# CP2200.net
KiCad netlist of a schematic drawn in Altium Designer
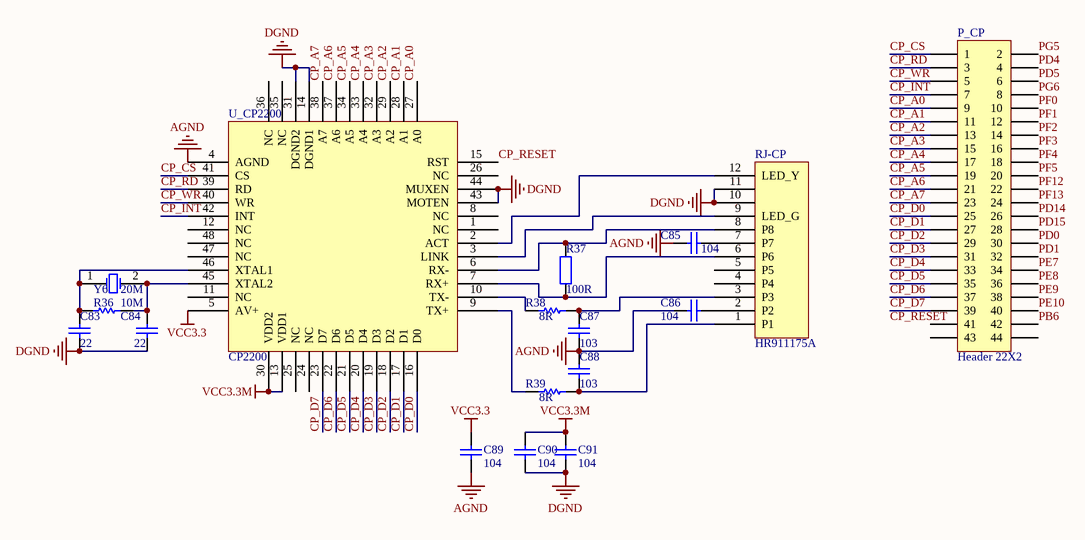
[diagram p0: CP2200.SchDoc]

(export (version "E")
  (design (tool "Eeschema 10.0.6"))
  (components
    (comp (ref "C83")
      (value "22")
      (footprint "SMT-0603")
      (description "Capacitor")
      (fields (field (name "Comment") "Cap") (field (name "PUBLISHER") "Altium Limited"))
      (libsource (lib "Miscellaneous Devices") (part "Cap"))
    )
    (comp (ref "C84")
      (value "22")
      (footprint "SMT-0603")
      (description "Capacitor")
      (fields (field (name "Comment") "Cap") (field (name "PUBLISHER") "Altium Limited"))
      (libsource (lib "Miscellaneous Devices") (part "Cap"))
    )
    (comp (ref "C85")
      (value "104")
      (footprint "SMT-0603")
      (description "Capacitor")
      (fields (field (name "Comment") "Cap") (field (name "PUBLISHER") "Altium Limited"))
      (libsource (lib "Miscellaneous Devices") (part "Cap"))
    )
    (comp (ref "C86")
      (value "104")
      (footprint "SMT-0603")
      (description "Capacitor")
      (fields (field (name "Comment") "Cap") (field (name "PUBLISHER") "Altium Limited"))
      (libsource (lib "Miscellaneous Devices") (part "Cap"))
    )
    (comp (ref "C87")
      (value "103")
      (footprint "SMT-0603")
      (description "Capacitor")
      (fields (field (name "Comment") "Cap") (field (name "PUBLISHER") "Altium Limited"))
      (libsource (lib "Miscellaneous Devices") (part "Cap"))
    )
    (comp (ref "C88")
      (value "103")
      (footprint "SMT-0603")
      (description "Capacitor")
      (fields (field (name "Comment") "Cap") (field (name "PUBLISHER") "Altium Limited"))
      (libsource (lib "Miscellaneous Devices") (part "Cap"))
    )
    (comp (ref "C89")
      (value "104")
      (footprint "SMT-0603")
      (description "Capacitor")
      (fields (field (name "Comment") "Cap") (field (name "PUBLISHER") "Altium Limited"))
      (libsource (lib "Miscellaneous Devices") (part "Cap"))
    )
    (comp (ref "C90")
      (value "104")
      (footprint "SMT-0603")
      (description "Capacitor")
      (fields (field (name "Comment") "Cap") (field (name "PUBLISHER") "Altium Limited"))
      (libsource (lib "Miscellaneous Devices") (part "Cap"))
    )
    (comp (ref "C91")
      (value "104")
      (footprint "SMT-0603")
      (description "Capacitor")
      (fields (field (name "Comment") "Cap") (field (name "PUBLISHER") "Altium Limited"))
      (libsource (lib "Miscellaneous Devices") (part "Cap"))
    )
    (comp (ref "P_CP")
      (value "Header 22X2")
      (footprint "HDR2X22")
      (description "Header, 22-Pin, Dual row")
      (fields (field (name "PUBLISHER") "Altium Limited"))
      (libsource (lib "Miscellaneous Connectors") (part "Header 22X2"))
    )
    (comp (ref "R36")
      (value "10M")
      (footprint "SMT-0603")
      (description "Resistor")
      (fields (field (name "Comment") "Res1") (field (name "PUBLISHER") "Altium Limited"))
      (libsource (lib "Miscellaneous Devices") (part "Res1"))
    )
    (comp (ref "R37")
      (value "100R")
      (footprint "SMT-0603")
      (description "Resistor")
      (fields (field (name "Comment") "Res2") (field (name "PUBLISHER") "Altium Limited"))
      (libsource (lib "Miscellaneous Devices") (part "Res2"))
    )
    (comp (ref "R38")
      (value "8R")
      (footprint "SMT-0603")
      (description "Resistor")
      (fields (field (name "Comment") "Res1") (field (name "PUBLISHER") "Altium Limited"))
      (libsource (lib "Miscellaneous Devices") (part "Res1"))
    )
    (comp (ref "R39")
      (value "8R")
      (footprint "SMT-0603")
      (description "Resistor")
      (fields (field (name "Comment") "Res1") (field (name "PUBLISHER") "Altium Limited"))
      (libsource (lib "Miscellaneous Devices") (part "Res1"))
    )
    (comp (ref "RJ-CP")
      (value "HR911175A")
      (footprint "RJ45-LED")
      (libsource (lib "STM_ALL") (part "RJ-45 HR911175A"))
    )
    (comp (ref "U_CP2200") (value "CP2200") (footprint "LQFP48L") (libsource (lib "STM_ALL") (part "CP2200")))
    (comp (ref "Y6")
      (value "20M")
      (footprint "D-CRYSTAL_UPRIGHT")
      (description "Crystal Oscillator")
      (fields (field (name "PUBLISHER") "Altium Limited"))
      (libsource (lib "Miscellaneous Devices") (part "XTAL"))
    )
  )
  (nets
    (net (code "1") (name "/CP_A0") (class "Default")
      (node (ref "P_CP") (pin "9") (pinfunction "9_9") (pintype "passive"))
      (node (ref "U_CP2200") (pin "27") (pinfunction "A0_27") (pintype "passive"))
    )
    (net (code "2") (name "/CP_A1") (class "Default")
      (node (ref "P_CP") (pin "11") (pinfunction "11_11") (pintype "passive"))
      (node (ref "U_CP2200") (pin "28") (pinfunction "A1_28") (pintype "passive"))
    )
    (net (code "3") (name "/CP_A2") (class "Default")
      (node (ref "P_CP") (pin "13") (pinfunction "13_13") (pintype "passive"))
      (node (ref "U_CP2200") (pin "29") (pinfunction "A2_29") (pintype "passive"))
    )
    (net (code "4") (name "/CP_A3") (class "Default")
      (node (ref "P_CP") (pin "15") (pinfunction "15_15") (pintype "passive"))
      (node (ref "U_CP2200") (pin "32") (pinfunction "A3_32") (pintype "passive"))
    )
    (net (code "5") (name "/CP_A4") (class "Default")
      (node (ref "P_CP") (pin "17") (pinfunction "17_17") (pintype "passive"))
      (node (ref "U_CP2200") (pin "33") (pinfunction "A4_33") (pintype "passive"))
    )
    (net (code "6") (name "/CP_A5") (class "Default")
      (node (ref "P_CP") (pin "19") (pinfunction "19_19") (pintype "passive"))
      (node (ref "U_CP2200") (pin "34") (pinfunction "A5_34") (pintype "passive"))
    )
    (net (code "7") (name "/CP_A6") (class "Default")
      (node (ref "P_CP") (pin "21") (pinfunction "21_21") (pintype "passive"))
      (node (ref "U_CP2200") (pin "37") (pinfunction "A6_37") (pintype "passive"))
    )
    (net (code "8") (name "/CP_A7") (class "Default")
      (node (ref "P_CP") (pin "23") (pinfunction "23_23") (pintype "passive"))
      (node (ref "U_CP2200") (pin "38") (pinfunction "A7_38") (pintype "passive"))
    )
    (net (code "9") (name "/CP_CS") (class "Default")
      (node (ref "P_CP") (pin "1") (pinfunction "1_1") (pintype "passive"))
      (node (ref "U_CP2200") (pin "41") (pinfunction "CS_41") (pintype "passive"))
    )
    (net (code "10") (name "/CP_D0") (class "Default")
      (node (ref "P_CP") (pin "25") (pinfunction "25_25") (pintype "passive"))
      (node (ref "U_CP2200") (pin "16") (pinfunction "D0_16") (pintype "passive"))
    )
    (net (code "11") (name "/CP_D1") (class "Default")
      (node (ref "P_CP") (pin "27") (pinfunction "27_27") (pintype "passive"))
      (node (ref "U_CP2200") (pin "17") (pinfunction "D1_17") (pintype "passive"))
    )
    (net (code "12") (name "/CP_D2") (class "Default")
      (node (ref "P_CP") (pin "29") (pinfunction "29_29") (pintype "passive"))
      (node (ref "U_CP2200") (pin "18") (pinfunction "D2_18") (pintype "passive"))
    )
    (net (code "13") (name "/CP_D3") (class "Default")
      (node (ref "P_CP") (pin "31") (pinfunction "31_31") (pintype "passive"))
      (node (ref "U_CP2200") (pin "19") (pinfunction "D3_19") (pintype "passive"))
    )
    (net (code "14") (name "/CP_D4") (class "Default")
      (node (ref "P_CP") (pin "33") (pinfunction "33_33") (pintype "passive"))
      (node (ref "U_CP2200") (pin "20") (pinfunction "D4_20") (pintype "passive"))
    )
    (net (code "15") (name "/CP_D5") (class "Default")
      (node (ref "P_CP") (pin "35") (pinfunction "35_35") (pintype "passive"))
      (node (ref "U_CP2200") (pin "21") (pinfunction "D5_21") (pintype "passive"))
    )
    (net (code "16") (name "/CP_D6") (class "Default")
      (node (ref "P_CP") (pin "37") (pinfunction "37_37") (pintype "passive"))
      (node (ref "U_CP2200") (pin "22") (pinfunction "D6_22") (pintype "passive"))
    )
    (net (code "17") (name "/CP_D7") (class "Default")
      (node (ref "P_CP") (pin "39") (pinfunction "39_39") (pintype "passive"))
      (node (ref "U_CP2200") (pin "23") (pinfunction "D7_23") (pintype "passive"))
    )
    (net (code "18") (name "/CP_INT") (class "Default")
      (node (ref "P_CP") (pin "7") (pinfunction "7_7") (pintype "passive"))
      (node (ref "U_CP2200") (pin "42") (pinfunction "INT_42") (pintype "passive"))
    )
    (net (code "19") (name "/CP_RD") (class "Default")
      (node (ref "P_CP") (pin "3") (pinfunction "3_3") (pintype "passive"))
      (node (ref "U_CP2200") (pin "39") (pinfunction "RD_39") (pintype "passive"))
    )
    (net (code "20") (name "/CP_RESET") (class "Default")
      (node (ref "U_CP2200") (pin "15") (pinfunction "RST_15") (pintype "passive"))
    )
    (net (code "21") (name "/CP_WR") (class "Default")
      (node (ref "P_CP") (pin "5") (pinfunction "5_5") (pintype "passive"))
      (node (ref "U_CP2200") (pin "40") (pinfunction "WR_40") (pintype "passive"))
    )
    (net (code "22") (name "/PB6") (class "Default")
      (node (ref "P_CP") (pin "42") (pinfunction "42_42") (pintype "passive"))
    )
    (net (code "23") (name "/PD0") (class "Default")
      (node (ref "P_CP") (pin "30") (pinfunction "30_30") (pintype "passive"))
    )
    (net (code "24") (name "/PD1") (class "Default")
      (node (ref "P_CP") (pin "32") (pinfunction "32_32") (pintype "passive"))
    )
    (net (code "25") (name "/PD4") (class "Default")
      (node (ref "P_CP") (pin "4") (pinfunction "4_4") (pintype "passive"))
    )
    (net (code "26") (name "/PD5") (class "Default")
      (node (ref "P_CP") (pin "6") (pinfunction "6_6") (pintype "passive"))
    )
    (net (code "27") (name "/PD14") (class "Default")
      (node (ref "P_CP") (pin "26") (pinfunction "26_26") (pintype "passive"))
    )
    (net (code "28") (name "/PD15") (class "Default")
      (node (ref "P_CP") (pin "28") (pinfunction "28_28") (pintype "passive"))
    )
    (net (code "29") (name "/PE7") (class "Default")
      (node (ref "P_CP") (pin "34") (pinfunction "34_34") (pintype "passive"))
    )
    (net (code "30") (name "/PE8") (class "Default")
      (node (ref "P_CP") (pin "36") (pinfunction "36_36") (pintype "passive"))
    )
    (net (code "31") (name "/PE9") (class "Default")
      (node (ref "P_CP") (pin "38") (pinfunction "38_38") (pintype "passive"))
    )
    (net (code "32") (name "/PE10") (class "Default")
      (node (ref "P_CP") (pin "40") (pinfunction "40_40") (pintype "passive"))
    )
    (net (code "33") (name "/PF0") (class "Default")
      (node (ref "P_CP") (pin "10") (pinfunction "10_10") (pintype "passive"))
    )
    (net (code "34") (name "/PF1") (class "Default")
      (node (ref "P_CP") (pin "12") (pinfunction "12_12") (pintype "passive"))
    )
    (net (code "35") (name "/PF2") (class "Default")
      (node (ref "P_CP") (pin "14") (pinfunction "14_14") (pintype "passive"))
    )
    (net (code "36") (name "/PF3") (class "Default")
      (node (ref "P_CP") (pin "16") (pinfunction "16_16") (pintype "passive"))
    )
    (net (code "37") (name "/PF4") (class "Default")
      (node (ref "P_CP") (pin "18") (pinfunction "18_18") (pintype "passive"))
    )
    (net (code "38") (name "/PF5") (class "Default")
      (node (ref "P_CP") (pin "20") (pinfunction "20_20") (pintype "passive"))
    )
    (net (code "39") (name "/PF12") (class "Default")
      (node (ref "P_CP") (pin "22") (pinfunction "22_22") (pintype "passive"))
    )
    (net (code "40") (name "/PF13") (class "Default")
      (node (ref "P_CP") (pin "24") (pinfunction "24_24") (pintype "passive"))
    )
    (net (code "41") (name "/PG5") (class "Default")
      (node (ref "P_CP") (pin "2") (pinfunction "2_2") (pintype "passive"))
    )
    (net (code "42") (name "/PG6") (class "Default")
      (node (ref "P_CP") (pin "8") (pinfunction "8_8") (pintype "passive"))
    )
    (net (code "43") (name "AGND") (class "Default")
      (node (ref "C85") (pin "1") (pinfunction "1_1") (pintype "passive"))
      (node (ref "C86") (pin "1") (pinfunction "1_1") (pintype "passive"))
      (node (ref "C87") (pin "2") (pinfunction "2_2") (pintype "passive"))
      (node (ref "C88") (pin "1") (pinfunction "1_1") (pintype "passive"))
      (node (ref "C89") (pin "1") (pinfunction "1_1") (pintype "passive"))
      (node (ref "U_CP2200") (pin "4") (pinfunction "AGND_4") (pintype "passive"))
    )
    (net (code "44") (name "DGND") (class "Default")
      (node (ref "C83") (pin "1") (pinfunction "1_1") (pintype "passive"))
      (node (ref "C84") (pin "1") (pinfunction "1_1") (pintype "passive"))
      (node (ref "C90") (pin "1") (pinfunction "1_1") (pintype "passive"))
      (node (ref "C91") (pin "1") (pinfunction "1_1") (pintype "passive"))
      (node (ref "RJ-CP") (pin "10") (pintype "passive"))
      (node (ref "RJ-CP") (pin "11") (pintype "passive"))
      (node (ref "U_CP2200") (pin "14") (pinfunction "DGND1_14") (pintype "passive"))
      (node (ref "U_CP2200") (pin "31") (pinfunction "DGND2_31") (pintype "passive"))
      (node (ref "U_CP2200") (pin "43") (pinfunction "MOTEN_43") (pintype "passive"))
      (node (ref "U_CP2200") (pin "44") (pinfunction "MUXEN_44") (pintype "passive"))
    )
    (net (code "45") (name "Net-(RJ-CP-LED_G)") (class "Default")
      (node (ref "RJ-CP") (pin "9") (pinfunction "LED_G_9") (pintype "passive"))
      (node (ref "U_CP2200") (pin "3") (pinfunction "LINK_3") (pintype "passive"))
    )
    (net (code "46") (name "Net-(RJ-CP-LED_Y)") (class "Default")
      (node (ref "RJ-CP") (pin "12") (pinfunction "LED_Y_12") (pintype "passive"))
      (node (ref "U_CP2200") (pin "2") (pinfunction "ACT_2") (pintype "passive"))
    )
    (net (code "47") (name "Net-(RJ-CP-P1)") (class "Default")
      (node (ref "C88") (pin "2") (pinfunction "2_2") (pintype "passive"))
      (node (ref "R39") (pin "2") (pinfunction "2_2") (pintype "passive"))
      (node (ref "RJ-CP") (pin "1") (pinfunction "P1_1") (pintype "passive"))
    )
    (net (code "48") (name "Net-(RJ-CP-P2)") (class "Default")
      (node (ref "C86") (pin "2") (pinfunction "2_2") (pintype "passive"))
      (node (ref "RJ-CP") (pin "2") (pinfunction "P2_2") (pintype "passive"))
    )
    (net (code "49") (name "Net-(RJ-CP-P3)") (class "Default")
      (node (ref "C87") (pin "1") (pinfunction "1_1") (pintype "passive"))
      (node (ref "R38") (pin "2") (pinfunction "2_2") (pintype "passive"))
      (node (ref "RJ-CP") (pin "3") (pinfunction "P3_3") (pintype "passive"))
    )
    (net (code "50") (name "Net-(RJ-CP-P6)") (class "Default")
      (node (ref "R37") (pin "1") (pinfunction "1_1") (pintype "passive"))
      (node (ref "RJ-CP") (pin "6") (pinfunction "P6_6") (pintype "passive"))
      (node (ref "U_CP2200") (pin "7") (pinfunction "RX+_7") (pintype "passive"))
    )
    (net (code "51") (name "Net-(RJ-CP-P7)") (class "Default")
      (node (ref "C85") (pin "2") (pinfunction "2_2") (pintype "passive"))
      (node (ref "RJ-CP") (pin "7") (pinfunction "P7_7") (pintype "passive"))
    )
    (net (code "52") (name "Net-(RJ-CP-P8)") (class "Default")
      (node (ref "R37") (pin "2") (pinfunction "2_2") (pintype "passive"))
      (node (ref "RJ-CP") (pin "8") (pinfunction "P8_8") (pintype "passive"))
      (node (ref "U_CP2200") (pin "6") (pinfunction "RX-_6") (pintype "passive"))
    )
    (net (code "53") (name "Net-(U_CP2200-TX+)") (class "Default")
      (node (ref "R39") (pin "1") (pinfunction "1_1") (pintype "passive"))
      (node (ref "U_CP2200") (pin "9") (pinfunction "TX+_9") (pintype "passive"))
    )
    (net (code "54") (name "Net-(U_CP2200-TX-)") (class "Default")
      (node (ref "R38") (pin "1") (pinfunction "1_1") (pintype "passive"))
      (node (ref "U_CP2200") (pin "10") (pinfunction "TX-_10") (pintype "passive"))
    )
    (net (code "55") (name "Net-(U_CP2200-XTAL1)") (class "Default")
      (node (ref "C83") (pin "2") (pinfunction "2_2") (pintype "passive"))
      (node (ref "R36") (pin "1") (pinfunction "1_1") (pintype "passive"))
      (node (ref "U_CP2200") (pin "46") (pinfunction "XTAL1_46") (pintype "passive"))
      (node (ref "Y6") (pin "1") (pinfunction "OSC1_1") (pintype "passive"))
    )
    (net (code "56") (name "Net-(U_CP2200-XTAL2)") (class "Default")
      (node (ref "C84") (pin "2") (pinfunction "2_2") (pintype "passive"))
      (node (ref "R36") (pin "2") (pinfunction "2_2") (pintype "passive"))
      (node (ref "U_CP2200") (pin "45") (pinfunction "XTAL2_45") (pintype "passive"))
      (node (ref "Y6") (pin "2") (pinfunction "OSC2_2") (pintype "passive"))
    )
    (net (code "57") (name "VCC3.3") (class "Default")
      (node (ref "C89") (pin "2") (pinfunction "2_2") (pintype "passive"))
      (node (ref "U_CP2200") (pin "5") (pinfunction "AV+_5") (pintype "passive"))
    )
    (net (code "58") (name "VCC3.3M") (class "Default")
      (node (ref "C90") (pin "2") (pinfunction "2_2") (pintype "passive"))
      (node (ref "C91") (pin "2") (pinfunction "2_2") (pintype "passive"))
      (node (ref "U_CP2200") (pin "13") (pinfunction "VDD1_13") (pintype "passive"))
      (node (ref "U_CP2200") (pin "30") (pinfunction "VDD2_30") (pintype "passive"))
    )
    (net (code "59") (name "unconnected-(P_CP-Pad41)") (class "Default")
      (node (ref "P_CP") (pin "41") (pinfunction "41_41") (pintype "passive"))
    )
    (net (code "60") (name "unconnected-(P_CP-Pad43)") (class "Default")
      (node (ref "P_CP") (pin "43") (pinfunction "43_43") (pintype "passive"))
    )
    (net (code "61") (name "unconnected-(P_CP-Pad44)") (class "Default")
      (node (ref "P_CP") (pin "44") (pinfunction "44_44") (pintype "passive"))
    )
    (net (code "62") (name "unconnected-(RJ-CP-P4-Pad4)") (class "Default")
      (node (ref "RJ-CP") (pin "4") (pinfunction "P4_4") (pintype "passive"))
    )
    (net (code "63") (name "unconnected-(RJ-CP-P5-Pad5)") (class "Default")
      (node (ref "RJ-CP") (pin "5") (pinfunction "P5_5") (pintype "passive"))
    )
    (net (code "64") (name "unconnected-(U_CP2200-NC-Pad1)") (class "Default")
      (node (ref "U_CP2200") (pin "1") (pinfunction "NC_1") (pintype "passive"))
    )
    (net (code "65") (name "unconnected-(U_CP2200-NC-Pad8)") (class "Default")
      (node (ref "U_CP2200") (pin "8") (pinfunction "NC_8") (pintype "passive"))
    )
    (net (code "66") (name "unconnected-(U_CP2200-NC-Pad11)") (class "Default")
      (node (ref "U_CP2200") (pin "11") (pinfunction "NC_11") (pintype "passive"))
    )
    (net (code "67") (name "unconnected-(U_CP2200-NC-Pad12)") (class "Default")
      (node (ref "U_CP2200") (pin "12") (pinfunction "NC_12") (pintype "passive"))
    )
    (net (code "68") (name "unconnected-(U_CP2200-NC-Pad24)") (class "Default")
      (node (ref "U_CP2200") (pin "24") (pinfunction "NC_24") (pintype "passive"))
    )
    (net (code "69") (name "unconnected-(U_CP2200-NC-Pad25)") (class "Default")
      (node (ref "U_CP2200") (pin "25") (pinfunction "NC_25") (pintype "passive"))
    )
    (net (code "70") (name "unconnected-(U_CP2200-NC-Pad26)") (class "Default")
      (node (ref "U_CP2200") (pin "26") (pinfunction "NC_26") (pintype "passive"))
    )
    (net (code "71") (name "unconnected-(U_CP2200-NC-Pad35)") (class "Default")
      (node (ref "U_CP2200") (pin "35") (pinfunction "NC_35") (pintype "passive"))
    )
    (net (code "72") (name "unconnected-(U_CP2200-NC-Pad36)") (class "Default")
      (node (ref "U_CP2200") (pin "36") (pinfunction "NC_36") (pintype "passive"))
    )
    (net (code "73") (name "unconnected-(U_CP2200-NC-Pad47)") (class "Default")
      (node (ref "U_CP2200") (pin "47") (pinfunction "NC_47") (pintype "passive"))
    )
    (net (code "74") (name "unconnected-(U_CP2200-NC-Pad48)") (class "Default")
      (node (ref "U_CP2200") (pin "48") (pinfunction "NC_48") (pintype "passive"))
    )
  )
)
